# 3DoT-Hexy-Shield.net
KiCad netlist of a schematic drawn in EAGLE
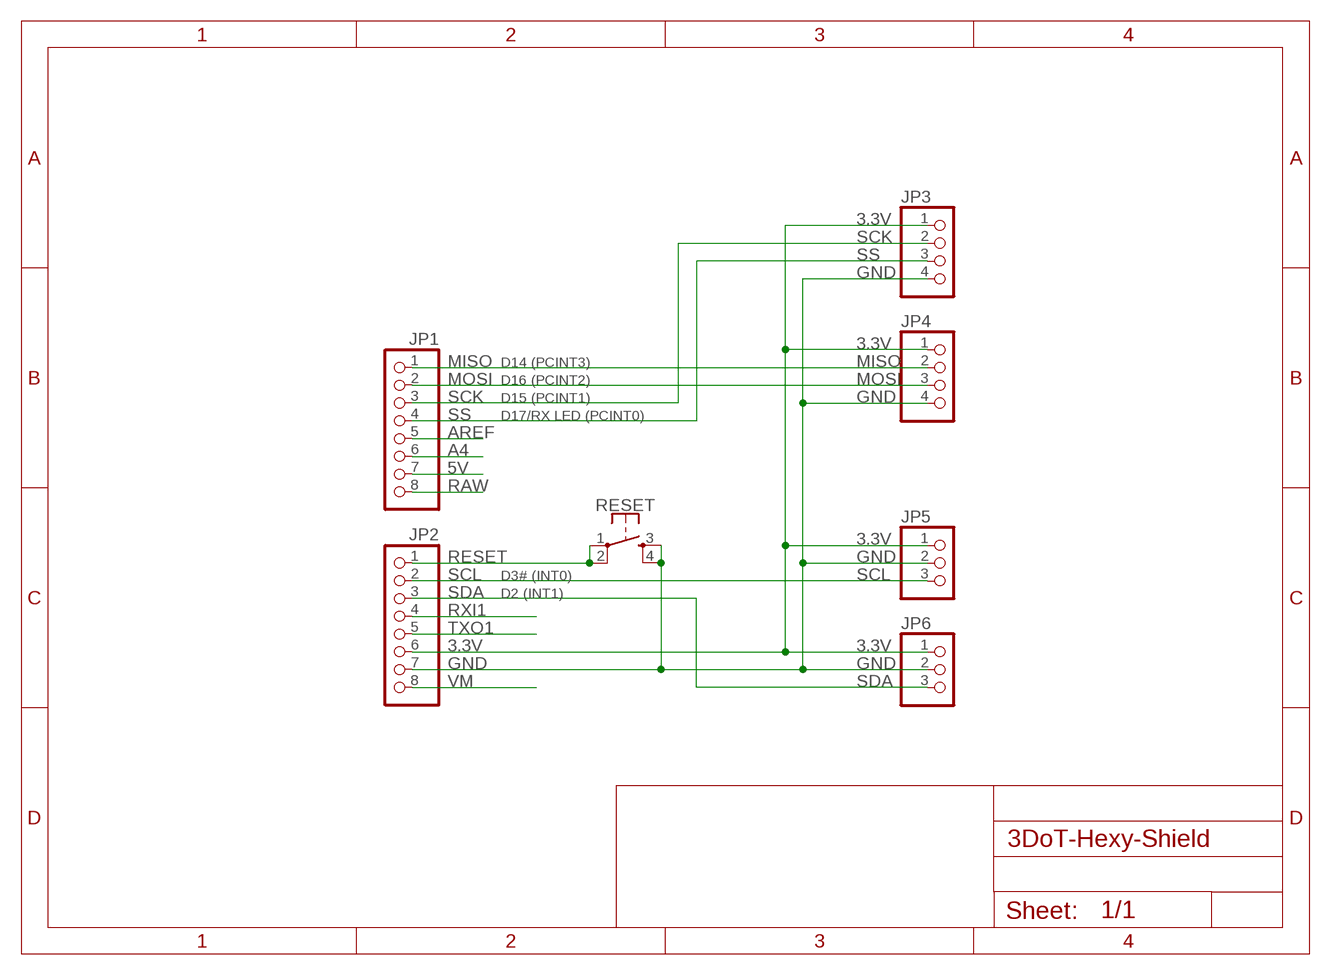
[diagram p0: schematic, sheet 1]

(export (version "E")
  (design (tool "Eeschema 10.0.6"))
  (components
    (comp (ref "JP1")
      (value "PINHD-1X8")
      (footprint "eagle-import:1X08")
      (libsource (lib "eagle-import") (part "PINHD-1X8"))
    )
    (comp (ref "JP2")
      (value "PINHD-1X8")
      (footprint "eagle-import:1X08")
      (libsource (lib "eagle-import") (part "PINHD-1X8"))
    )
    (comp (ref "JP3")
      (value "PINHD-1X4")
      (footprint "eagle-import:1X04")
      (libsource (lib "eagle-import") (part "PINHD-1X4"))
    )
    (comp (ref "JP4")
      (value "PINHD-1X4")
      (footprint "eagle-import:1X04")
      (libsource (lib "eagle-import") (part "PINHD-1X4"))
    )
    (comp (ref "JP5")
      (value "PINHD-1X3")
      (footprint "eagle-import:1X03")
      (libsource (lib "eagle-import") (part "PINHD-1X3"))
    )
    (comp (ref "JP6")
      (value "PINHD-1X3")
      (footprint "eagle-import:1X03")
      (libsource (lib "eagle-import") (part "PINHD-1X3"))
    )
    (comp (ref "RESET")
      (value "MOMENTARY-SWITCH-SPST-2-SMD-5.2MM")
      (footprint "eagle-import:TACTILE_SWITCH_SMD_5.2MM")
      (libsource (lib "eagle-import") (part "MOMENTARY-SWITCH-SPST-2-SMD-5.2MM"))
    )
  )
  (nets
    (net (code "1") (name "/3.3V") (class "Default")
      (node (ref "JP2") (pin "6") (pinfunction "6_6") (pintype "passive"))
      (node (ref "JP3") (pin "1") (pinfunction "1_1") (pintype "passive"))
      (node (ref "JP4") (pin "1") (pinfunction "1_1") (pintype "passive"))
      (node (ref "JP5") (pin "1") (pinfunction "1_1") (pintype "passive"))
      (node (ref "JP6") (pin "1") (pinfunction "1_1") (pintype "passive"))
    )
    (net (code "2") (name "/5V") (class "Default")
      (node (ref "JP1") (pin "7") (pinfunction "7_7") (pintype "passive"))
    )
    (net (code "3") (name "/A4") (class "Default")
      (node (ref "JP1") (pin "6") (pinfunction "6_6") (pintype "passive"))
    )
    (net (code "4") (name "/AREF") (class "Default")
      (node (ref "JP1") (pin "5") (pinfunction "5_5") (pintype "passive"))
    )
    (net (code "5") (name "/GND") (class "Default")
      (node (ref "JP2") (pin "7") (pinfunction "7_7") (pintype "passive"))
      (node (ref "JP3") (pin "4") (pinfunction "4_4") (pintype "passive"))
      (node (ref "JP4") (pin "4") (pinfunction "4_4") (pintype "passive"))
      (node (ref "JP5") (pin "2") (pinfunction "2_2") (pintype "passive"))
      (node (ref "JP6") (pin "2") (pinfunction "2_2") (pintype "passive"))
      (node (ref "RESET") (pin "3") (pinfunction "3_3") (pintype "passive"))
      (node (ref "RESET") (pin "4") (pinfunction "4_4") (pintype "passive"))
    )
    (net (code "6") (name "/MISO") (class "Default")
      (node (ref "JP1") (pin "1") (pinfunction "1_1") (pintype "passive"))
      (node (ref "JP4") (pin "2") (pinfunction "2_2") (pintype "passive"))
    )
    (net (code "7") (name "/MOSI") (class "Default")
      (node (ref "JP1") (pin "2") (pinfunction "2_2") (pintype "passive"))
      (node (ref "JP4") (pin "3") (pinfunction "3_3") (pintype "passive"))
    )
    (net (code "8") (name "/RAW") (class "Default")
      (node (ref "JP1") (pin "8") (pinfunction "8_8") (pintype "passive"))
    )
    (net (code "9") (name "/RESET") (class "Default")
      (node (ref "JP2") (pin "1") (pinfunction "1_1") (pintype "passive"))
      (node (ref "RESET") (pin "1") (pinfunction "1_1") (pintype "passive"))
      (node (ref "RESET") (pin "2") (pinfunction "2_2") (pintype "passive"))
    )
    (net (code "10") (name "/RXI1") (class "Default")
      (node (ref "JP2") (pin "4") (pinfunction "4_4") (pintype "passive"))
    )
    (net (code "11") (name "/SCK") (class "Default")
      (node (ref "JP1") (pin "3") (pinfunction "3_3") (pintype "passive"))
      (node (ref "JP3") (pin "2") (pinfunction "2_2") (pintype "passive"))
    )
    (net (code "12") (name "/SCL") (class "Default")
      (node (ref "JP2") (pin "2") (pinfunction "2_2") (pintype "passive"))
      (node (ref "JP5") (pin "3") (pinfunction "3_3") (pintype "passive"))
    )
    (net (code "13") (name "/SDA") (class "Default")
      (node (ref "JP2") (pin "3") (pinfunction "3_3") (pintype "passive"))
      (node (ref "JP6") (pin "3") (pinfunction "3_3") (pintype "passive"))
    )
    (net (code "14") (name "/SS") (class "Default")
      (node (ref "JP1") (pin "4") (pinfunction "4_4") (pintype "passive"))
      (node (ref "JP3") (pin "3") (pinfunction "3_3") (pintype "passive"))
    )
    (net (code "15") (name "/TXO1") (class "Default")
      (node (ref "JP2") (pin "5") (pinfunction "5_5") (pintype "passive"))
    )
    (net (code "16") (name "/VM") (class "Default")
      (node (ref "JP2") (pin "8") (pinfunction "8_8") (pintype "passive"))
    )
  )
)
